# bridge.net
KiCad netlist of a schematic drawn in Altium Designer
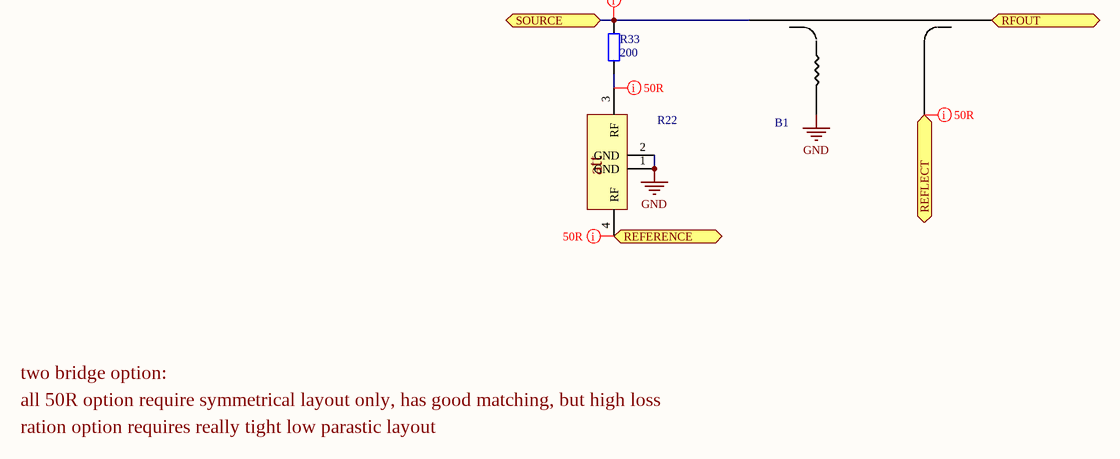
[diagram p0: bridge.SchDoc]

(export (version "E")
  (design (tool "Eeschema 10.0.6"))
  (components
    (comp (ref "B1") (value "BRIDGE") (footprint "BRIDGE-4") (libsource (lib "F4SDR") (part "BRIDGE")))
    (comp (ref "R22")
      (value "EXB24-RF-ATT")
      (footprint "EXB24AT-RF-ATT")
      (libsource (lib "F4SDR") (part "EXB24-RF-ATT"))
    )
    (comp (ref "R33")
      (value "200")
      (footprint "0201")
      (description "Resistor")
      (fields (field (name "PUBLISHER") "Altium Limited"))
      (libsource (lib "Miscellaneous Devices") (part "Res2"))
    )
  )
  (nets
    (net (code "1") (name "/REFERENCE") (class "Default")
      (node (ref "R22") (pin "4") (pinfunction "RF_4") (pintype "passive"))
    )
    (net (code "2") (name "/REFLECT") (class "Default")
      (node (ref "B1") (pin "COUPLE") (pinfunction "COUPLE_COUPLE") (pintype "passive"))
    )
    (net (code "3") (name "/RFOUT") (class "Default")
      (node (ref "B1") (pin "OUT") (pinfunction "OUT_OUT") (pintype "passive"))
    )
    (net (code "4") (name "/SOURCE") (class "Default")
      (node (ref "B1") (pin "SOURCE") (pinfunction "SOURCE_SOURCE") (pintype "passive"))
      (node (ref "R33") (pin "2") (pinfunction "2_2") (pintype "passive"))
    )
    (net (code "5") (name "GND") (class "Default")
      (node (ref "B1") (pin "GND") (pinfunction "GND_GND") (pintype "passive"))
      (node (ref "R22") (pin "1") (pinfunction "GND_1") (pintype "passive"))
      (node (ref "R22") (pin "2") (pinfunction "GND_2") (pintype "passive"))
    )
    (net (code "6") (name "Net-(R22-RF-Pad3)") (class "Default")
      (node (ref "R22") (pin "3") (pinfunction "RF_3") (pintype "passive"))
      (node (ref "R33") (pin "1") (pinfunction "1_1") (pintype "passive"))
    )
  )
)
